# led_matrix_cc.net
KiCad netlist of a schematic drawn in EAGLE
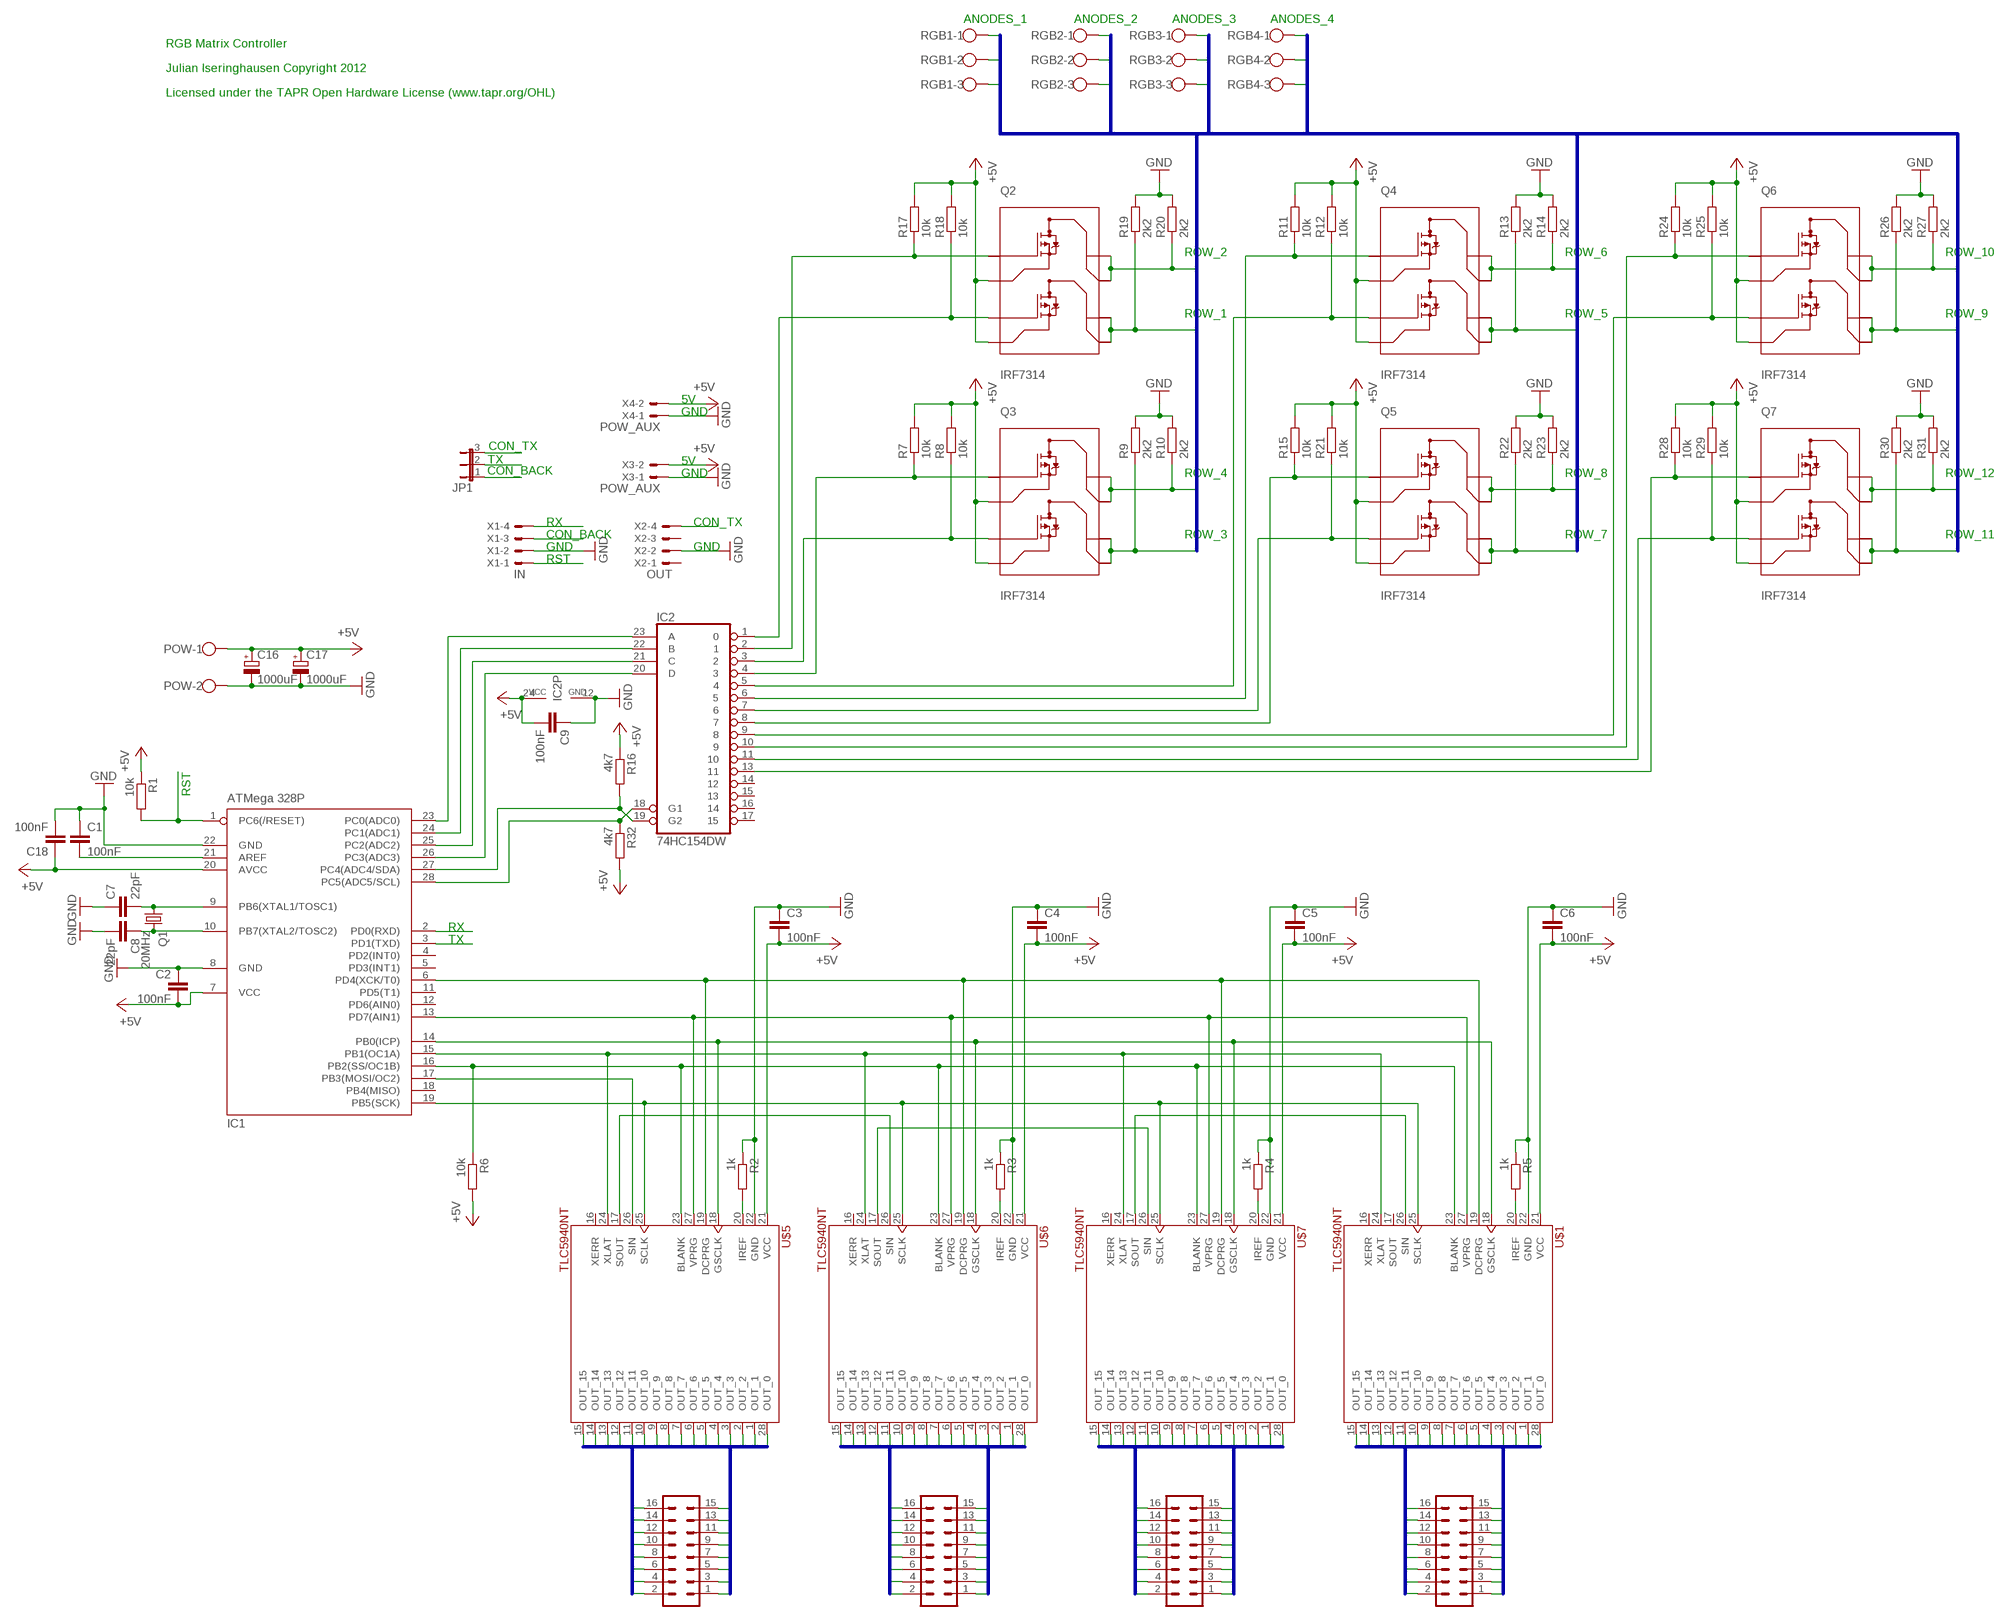
[diagram p0: schematic, sheet 1]

(export (version "E")
  (design (tool "Eeschema 10.0.6"))
  (components
    (comp (ref "C1")
      (value "100nF")
      (footprint "eagle-import:C1206")
      (libsource (lib "eagle-import") (part "C-EUC1206"))
    )
    (comp (ref "C2")
      (value "100nF")
      (footprint "eagle-import:C1206")
      (libsource (lib "eagle-import") (part "C-EUC1206"))
    )
    (comp (ref "C3")
      (value "100nF")
      (footprint "eagle-import:C1206")
      (libsource (lib "eagle-import") (part "C-EUC1206"))
    )
    (comp (ref "C4")
      (value "100nF")
      (footprint "eagle-import:C1206")
      (libsource (lib "eagle-import") (part "C-EUC1206"))
    )
    (comp (ref "C5")
      (value "100nF")
      (footprint "eagle-import:C1206")
      (libsource (lib "eagle-import") (part "C-EUC1206"))
    )
    (comp (ref "C6")
      (value "100nF")
      (footprint "eagle-import:C1206")
      (libsource (lib "eagle-import") (part "C-EUC1206"))
    )
    (comp (ref "C7")
      (value "22pF")
      (footprint "eagle-import:C1206")
      (libsource (lib "eagle-import") (part "C-EUC1206"))
    )
    (comp (ref "C8")
      (value "22pF")
      (footprint "eagle-import:C1206")
      (libsource (lib "eagle-import") (part "C-EUC1206"))
    )
    (comp (ref "C9")
      (value "100nF")
      (footprint "eagle-import:C1206")
      (libsource (lib "eagle-import") (part "C-EUC1206"))
    )
    (comp (ref "C16")
      (value "1000uF")
      (footprint "eagle-import:E5-10,5")
      (libsource (lib "eagle-import") (part "CPOL-EUE5-10.5"))
    )
    (comp (ref "C17")
      (value "1000uF")
      (footprint "eagle-import:E5-10,5")
      (libsource (lib "eagle-import") (part "CPOL-EUE5-10.5"))
    )
    (comp (ref "C18")
      (value "100nF")
      (footprint "eagle-import:C1206")
      (libsource (lib "eagle-import") (part "C-EUC1206"))
    )
    (comp (ref "CON_TLC_1")
      (value "ML16")
      (footprint "eagle-import:ML16")
      (libsource (lib "eagle-import") (part "ML16"))
    )
    (comp (ref "CON_TLC_2")
      (value "ML16")
      (footprint "eagle-import:ML16")
      (libsource (lib "eagle-import") (part "ML16"))
    )
    (comp (ref "CON_TLC_3")
      (value "ML16")
      (footprint "eagle-import:ML16")
      (libsource (lib "eagle-import") (part "ML16"))
    )
    (comp (ref "CON_TLC_4")
      (value "ML16")
      (footprint "eagle-import:ML16")
      (libsource (lib "eagle-import") (part "ML16"))
    )
    (comp (ref "IC1")
      (value "ATMega 328P")
      (footprint "eagle-import:DIL28-3")
      (libsource (lib "eagle-import") (part "MEGA8-P"))
    )
    (comp (ref "IC2")
      (value "74HC154DW")
      (footprint "eagle-import:SO24W")
      (libsource (lib "eagle-import") (part "74154DWHC"))
    )
    (comp (ref "JP1")
      (value "JP2E")
      (footprint "eagle-import:JP2")
      (libsource (lib "eagle-import") (part "JP2E"))
    )
    (comp (ref "POW")
      (value "W237-102")
      (footprint "eagle-import:W237-102")
      (fields (field (name "MPN") "237-102"))
      (libsource (lib "eagle-import") (part "W237-102"))
    )
    (comp (ref "Q1")
      (value "20MHz")
      (footprint "eagle-import:HC49U70")
      (libsource (lib "eagle-import") (part "CRYSTALHC49U70"))
    )
    (comp (ref "Q2")
      (value "IRF7314")
      (footprint "eagle-import:TRANSISTOR-FET-MOD_SO08-IRF")
      (libsource (lib "eagle-import") (part "TRANSISTOR-FET-MOD_IRF7389"))
    )
    (comp (ref "Q3")
      (value "IRF7314")
      (footprint "eagle-import:TRANSISTOR-FET-MOD_SO08-IRF")
      (libsource (lib "eagle-import") (part "TRANSISTOR-FET-MOD_IRF7389"))
    )
    (comp (ref "Q4")
      (value "IRF7314")
      (footprint "eagle-import:TRANSISTOR-FET-MOD_SO08-IRF")
      (libsource (lib "eagle-import") (part "TRANSISTOR-FET-MOD_IRF7389"))
    )
    (comp (ref "Q5")
      (value "IRF7314")
      (footprint "eagle-import:TRANSISTOR-FET-MOD_SO08-IRF")
      (libsource (lib "eagle-import") (part "TRANSISTOR-FET-MOD_IRF7389"))
    )
    (comp (ref "Q6")
      (value "IRF7314")
      (footprint "eagle-import:TRANSISTOR-FET-MOD_SO08-IRF")
      (libsource (lib "eagle-import") (part "TRANSISTOR-FET-MOD_IRF7389"))
    )
    (comp (ref "Q7")
      (value "IRF7314")
      (footprint "eagle-import:TRANSISTOR-FET-MOD_SO08-IRF")
      (libsource (lib "eagle-import") (part "TRANSISTOR-FET-MOD_IRF7389"))
    )
    (comp (ref "R1")
      (value "10k")
      (footprint "eagle-import:R1206")
      (libsource (lib "eagle-import") (part "R-EU_R1206"))
    )
    (comp (ref "R2")
      (value "1k")
      (footprint "eagle-import:R1206")
      (libsource (lib "eagle-import") (part "R-EU_R1206"))
    )
    (comp (ref "R3")
      (value "1k")
      (footprint "eagle-import:R1206")
      (libsource (lib "eagle-import") (part "R-EU_R1206"))
    )
    (comp (ref "R4")
      (value "1k")
      (footprint "eagle-import:R1206")
      (libsource (lib "eagle-import") (part "R-EU_R1206"))
    )
    (comp (ref "R5")
      (value "1k")
      (footprint "eagle-import:R1206")
      (libsource (lib "eagle-import") (part "R-EU_R1206"))
    )
    (comp (ref "R6")
      (value "10k")
      (footprint "eagle-import:R1206")
      (libsource (lib "eagle-import") (part "R-EU_R1206"))
    )
    (comp (ref "R7")
      (value "10k")
      (footprint "eagle-import:RCL_R1206")
      (libsource (lib "eagle-import") (part "RCL_R-EU_R1206"))
    )
    (comp (ref "R8")
      (value "10k")
      (footprint "eagle-import:RCL_R1206")
      (libsource (lib "eagle-import") (part "RCL_R-EU_R1206"))
    )
    (comp (ref "R9")
      (value "2k2")
      (footprint "eagle-import:RCL_R1206")
      (libsource (lib "eagle-import") (part "RCL_R-EU_R1206"))
    )
    (comp (ref "R10")
      (value "2k2")
      (footprint "eagle-import:RCL_R1206")
      (libsource (lib "eagle-import") (part "RCL_R-EU_R1206"))
    )
    (comp (ref "R11")
      (value "10k")
      (footprint "eagle-import:RCL_R1206")
      (libsource (lib "eagle-import") (part "RCL_R-EU_R1206"))
    )
    (comp (ref "R12")
      (value "10k")
      (footprint "eagle-import:RCL_R1206")
      (libsource (lib "eagle-import") (part "RCL_R-EU_R1206"))
    )
    (comp (ref "R13")
      (value "2k2")
      (footprint "eagle-import:RCL_R1206")
      (libsource (lib "eagle-import") (part "RCL_R-EU_R1206"))
    )
    (comp (ref "R14")
      (value "2k2")
      (footprint "eagle-import:RCL_R1206")
      (libsource (lib "eagle-import") (part "RCL_R-EU_R1206"))
    )
    (comp (ref "R15")
      (value "10k")
      (footprint "eagle-import:RCL_R1206")
      (libsource (lib "eagle-import") (part "RCL_R-EU_R1206"))
    )
    (comp (ref "R16")
      (value "4k7")
      (footprint "eagle-import:R1206")
      (libsource (lib "eagle-import") (part "R-EU_R1206"))
    )
    (comp (ref "R17")
      (value "10k")
      (footprint "eagle-import:RCL_R1206")
      (libsource (lib "eagle-import") (part "RCL_R-EU_R1206"))
    )
    (comp (ref "R18")
      (value "10k")
      (footprint "eagle-import:RCL_R1206")
      (libsource (lib "eagle-import") (part "RCL_R-EU_R1206"))
    )
    (comp (ref "R19")
      (value "2k2")
      (footprint "eagle-import:RCL_R1206")
      (libsource (lib "eagle-import") (part "RCL_R-EU_R1206"))
    )
    (comp (ref "R20")
      (value "2k2")
      (footprint "eagle-import:RCL_R1206")
      (libsource (lib "eagle-import") (part "RCL_R-EU_R1206"))
    )
    (comp (ref "R21")
      (value "10k")
      (footprint "eagle-import:RCL_R1206")
      (libsource (lib "eagle-import") (part "RCL_R-EU_R1206"))
    )
    (comp (ref "R22")
      (value "2k2")
      (footprint "eagle-import:RCL_R1206")
      (libsource (lib "eagle-import") (part "RCL_R-EU_R1206"))
    )
    (comp (ref "R23")
      (value "2k2")
      (footprint "eagle-import:RCL_R1206")
      (libsource (lib "eagle-import") (part "RCL_R-EU_R1206"))
    )
    (comp (ref "R24")
      (value "10k")
      (footprint "eagle-import:RCL_R1206")
      (libsource (lib "eagle-import") (part "RCL_R-EU_R1206"))
    )
    (comp (ref "R25")
      (value "10k")
      (footprint "eagle-import:RCL_R1206")
      (libsource (lib "eagle-import") (part "RCL_R-EU_R1206"))
    )
    (comp (ref "R26")
      (value "2k2")
      (footprint "eagle-import:RCL_R1206")
      (libsource (lib "eagle-import") (part "RCL_R-EU_R1206"))
    )
    (comp (ref "R27")
      (value "2k2")
      (footprint "eagle-import:RCL_R1206")
      (libsource (lib "eagle-import") (part "RCL_R-EU_R1206"))
    )
    (comp (ref "R28")
      (value "10k")
      (footprint "eagle-import:RCL_R1206")
      (libsource (lib "eagle-import") (part "RCL_R-EU_R1206"))
    )
    (comp (ref "R29")
      (value "10k")
      (footprint "eagle-import:RCL_R1206")
      (libsource (lib "eagle-import") (part "RCL_R-EU_R1206"))
    )
    (comp (ref "R30")
      (value "2k2")
      (footprint "eagle-import:RCL_R1206")
      (libsource (lib "eagle-import") (part "RCL_R-EU_R1206"))
    )
    (comp (ref "R31")
      (value "2k2")
      (footprint "eagle-import:RCL_R1206")
      (libsource (lib "eagle-import") (part "RCL_R-EU_R1206"))
    )
    (comp (ref "R32")
      (value "4k7")
      (footprint "eagle-import:R1206")
      (libsource (lib "eagle-import") (part "R-EU_R1206"))
    )
    (comp (ref "RGB1")
      (value "W237-103")
      (footprint "eagle-import:W237-103")
      (fields (field (name "MPN") "237-103"))
      (libsource (lib "eagle-import") (part "W237-103"))
    )
    (comp (ref "RGB2")
      (value "W237-103")
      (footprint "eagle-import:W237-103")
      (fields (field (name "MPN") "237-103"))
      (libsource (lib "eagle-import") (part "W237-103"))
    )
    (comp (ref "RGB3")
      (value "W237-103")
      (footprint "eagle-import:W237-103")
      (fields (field (name "MPN") "237-103"))
      (libsource (lib "eagle-import") (part "W237-103"))
    )
    (comp (ref "RGB4")
      (value "W237-103")
      (footprint "eagle-import:W237-103")
      (fields (field (name "MPN") "237-103"))
      (libsource (lib "eagle-import") (part "W237-103"))
    )
    (comp (ref "U$1")
      (value "TLC5940NT")
      (footprint "eagle-import:TLC5940_DIP-28")
      (libsource (lib "eagle-import") (part "TLC5940_TLC5940NT"))
    )
    (comp (ref "U$5")
      (value "TLC5940NT")
      (footprint "eagle-import:TLC5940_DIP-28")
      (libsource (lib "eagle-import") (part "TLC5940_TLC5940NT"))
    )
    (comp (ref "U$6")
      (value "TLC5940NT")
      (footprint "eagle-import:TLC5940_DIP-28")
      (libsource (lib "eagle-import") (part "TLC5940_TLC5940NT"))
    )
    (comp (ref "U$7")
      (value "TLC5940NT")
      (footprint "eagle-import:TLC5940_DIP-28")
      (libsource (lib "eagle-import") (part "TLC5940_TLC5940NT"))
    )
    (comp (ref "X1")
      (value "IN")
      (footprint "eagle-import:22-23-2041")
      (fields (field (name "MF") "MOLEX") (field (name "MPN") "22-23-2041"))
      (libsource (lib "eagle-import") (part "22-23-2041"))
    )
    (comp (ref "X2")
      (value "OUT")
      (footprint "eagle-import:22-23-2041")
      (fields (field (name "MF") "MOLEX") (field (name "MPN") "22-23-2041"))
      (libsource (lib "eagle-import") (part "22-23-2041"))
    )
    (comp (ref "X3")
      (value "POW_AUX")
      (footprint "eagle-import:22-23-2021")
      (fields (field (name "MF") "MOLEX") (field (name "MPN") "22-23-2021"))
      (libsource (lib "eagle-import") (part "22-23-2021"))
    )
    (comp (ref "X4")
      (value "POW_AUX")
      (footprint "eagle-import:22-23-2021")
      (fields (field (name "MF") "MOLEX") (field (name "MPN") "22-23-2021"))
      (libsource (lib "eagle-import") (part "22-23-2021"))
    )
  )
  (nets
    (net (code "1") (name "+5V") (class "Default")
      (node (ref "C16") (pin "+") (pinfunction "+_+") (pintype "passive"))
      (node (ref "C17") (pin "+") (pinfunction "+_+") (pintype "passive"))
      (node (ref "C18") (pin "1") (pinfunction "1_1") (pintype "passive"))
      (node (ref "C2") (pin "2") (pinfunction "2_2") (pintype "passive"))
      (node (ref "C3") (pin "2") (pinfunction "2_2") (pintype "passive"))
      (node (ref "C4") (pin "2") (pinfunction "2_2") (pintype "passive"))
      (node (ref "C5") (pin "2") (pinfunction "2_2") (pintype "passive"))
      (node (ref "C6") (pin "2") (pinfunction "2_2") (pintype "passive"))
      (node (ref "C9") (pin "2") (pinfunction "2_2") (pintype "passive"))
      (node (ref "IC1") (pin "20") (pinfunction "AVCC_20") (pintype "power_in"))
      (node (ref "IC1") (pin "7") (pinfunction "VCC_7") (pintype "power_in"))
      (node (ref "IC2") (pin "24") (pinfunction "VCC_24") (pintype "power_in"))
      (node (ref "POW") (pin "1") (pinfunction "KL_1") (pintype "passive"))
      (node (ref "Q2") (pin "1") (pinfunction "S1_1") (pintype "passive"))
      (node (ref "Q2") (pin "3") (pinfunction "S2_3") (pintype "passive"))
      (node (ref "Q3") (pin "1") (pinfunction "S1_1") (pintype "passive"))
      (node (ref "Q3") (pin "3") (pinfunction "S2_3") (pintype "passive"))
      (node (ref "Q4") (pin "1") (pinfunction "S1_1") (pintype "passive"))
      (node (ref "Q4") (pin "3") (pinfunction "S2_3") (pintype "passive"))
      (node (ref "Q5") (pin "1") (pinfunction "S1_1") (pintype "passive"))
      (node (ref "Q5") (pin "3") (pinfunction "S2_3") (pintype "passive"))
      (node (ref "Q6") (pin "1") (pinfunction "S1_1") (pintype "passive"))
      (node (ref "Q6") (pin "3") (pinfunction "S2_3") (pintype "passive"))
      (node (ref "Q7") (pin "1") (pinfunction "S1_1") (pintype "passive"))
      (node (ref "Q7") (pin "3") (pinfunction "S2_3") (pintype "passive"))
      (node (ref "R1") (pin "1") (pinfunction "1_1") (pintype "passive"))
      (node (ref "R11") (pin "2") (pinfunction "2_2") (pintype "passive"))
      (node (ref "R12") (pin "2") (pinfunction "2_2") (pintype "passive"))
      (node (ref "R15") (pin "2") (pinfunction "2_2") (pintype "passive"))
      (node (ref "R16") (pin "1") (pinfunction "1_1") (pintype "passive"))
      (node (ref "R17") (pin "2") (pinfunction "2_2") (pintype "passive"))
      (node (ref "R18") (pin "2") (pinfunction "2_2") (pintype "passive"))
      (node (ref "R21") (pin "2") (pinfunction "2_2") (pintype "passive"))
      (node (ref "R24") (pin "2") (pinfunction "2_2") (pintype "passive"))
      (node (ref "R25") (pin "2") (pinfunction "2_2") (pintype "passive"))
      (node (ref "R28") (pin "2") (pinfunction "2_2") (pintype "passive"))
      (node (ref "R29") (pin "2") (pinfunction "2_2") (pintype "passive"))
      (node (ref "R32") (pin "2") (pinfunction "2_2") (pintype "passive"))
      (node (ref "R6") (pin "2") (pinfunction "2_2") (pintype "passive"))
      (node (ref "R7") (pin "2") (pinfunction "2_2") (pintype "passive"))
      (node (ref "R8") (pin "2") (pinfunction "2_2") (pintype "passive"))
      (node (ref "U$1") (pin "21") (pinfunction "VCC_21") (pintype "power_in"))
      (node (ref "U$5") (pin "21") (pinfunction "VCC_21") (pintype "power_in"))
      (node (ref "U$6") (pin "21") (pinfunction "VCC_21") (pintype "power_in"))
      (node (ref "U$7") (pin "21") (pinfunction "VCC_21") (pintype "power_in"))
      (node (ref "X3") (pin "2") (pinfunction "S_2") (pintype "passive"))
      (node (ref "X4") (pin "2") (pinfunction "S_2") (pintype "passive"))
    )
    (net (code "2") (name "/CON_BACK") (class "Default")
      (node (ref "JP1") (pin "1") (pinfunction "1_1") (pintype "passive"))
      (node (ref "X1") (pin "3") (pinfunction "S_3") (pintype "passive"))
    )
    (net (code "3") (name "/CON_TX") (class "Default")
      (node (ref "JP1") (pin "3") (pinfunction "3_3") (pintype "passive"))
      (node (ref "X2") (pin "4") (pinfunction "S_4") (pintype "passive"))
    )
    (net (code "4") (name "/ROW1") (class "Default")
      (node (ref "Q2") (pin "5") (pinfunction "D2B_5") (pintype "passive"))
      (node (ref "Q2") (pin "6") (pinfunction "D2A_6") (pintype "passive"))
      (node (ref "R19") (pin "1") (pinfunction "1_1") (pintype "passive"))
      (node (ref "RGB1") (pin "1") (pinfunction "KL_1") (pintype "passive"))
    )
    (net (code "5") (name "/ROW2") (class "Default")
      (node (ref "Q2") (pin "7") (pinfunction "D1B_7") (pintype "passive"))
      (node (ref "Q2") (pin "8") (pinfunction "D1A_8") (pintype "passive"))
      (node (ref "R20") (pin "1") (pinfunction "1_1") (pintype "passive"))
      (node (ref "RGB1") (pin "2") (pinfunction "KL_2") (pintype "passive"))
    )
    (net (code "6") (name "/ROW3") (class "Default")
      (node (ref "Q3") (pin "5") (pinfunction "D2B_5") (pintype "passive"))
      (node (ref "Q3") (pin "6") (pinfunction "D2A_6") (pintype "passive"))
      (node (ref "R9") (pin "1") (pinfunction "1_1") (pintype "passive"))
      (node (ref "RGB1") (pin "3") (pinfunction "KL_3") (pintype "passive"))
    )
    (net (code "7") (name "/ROW4") (class "Default")
      (node (ref "Q3") (pin "7") (pinfunction "D1B_7") (pintype "passive"))
      (node (ref "Q3") (pin "8") (pinfunction "D1A_8") (pintype "passive"))
      (node (ref "R10") (pin "1") (pinfunction "1_1") (pintype "passive"))
      (node (ref "RGB2") (pin "1") (pinfunction "KL_1") (pintype "passive"))
    )
    (net (code "8") (name "/ROW5") (class "Default")
      (node (ref "Q4") (pin "5") (pinfunction "D2B_5") (pintype "passive"))
      (node (ref "Q4") (pin "6") (pinfunction "D2A_6") (pintype "passive"))
      (node (ref "R13") (pin "1") (pinfunction "1_1") (pintype "passive"))
      (node (ref "RGB2") (pin "2") (pinfunction "KL_2") (pintype "passive"))
    )
    (net (code "9") (name "/ROW6") (class "Default")
      (node (ref "Q4") (pin "7") (pinfunction "D1B_7") (pintype "passive"))
      (node (ref "Q4") (pin "8") (pinfunction "D1A_8") (pintype "passive"))
      (node (ref "R14") (pin "1") (pinfunction "1_1") (pintype "passive"))
      (node (ref "RGB2") (pin "3") (pinfunction "KL_3") (pintype "passive"))
    )
    (net (code "10") (name "/ROW7") (class "Default")
      (node (ref "Q5") (pin "5") (pinfunction "D2B_5") (pintype "passive"))
      (node (ref "Q5") (pin "6") (pinfunction "D2A_6") (pintype "passive"))
      (node (ref "R22") (pin "1") (pinfunction "1_1") (pintype "passive"))
      (node (ref "RGB3") (pin "1") (pinfunction "KL_1") (pintype "passive"))
    )
    (net (code "11") (name "/ROW8") (class "Default")
      (node (ref "Q5") (pin "7") (pinfunction "D1B_7") (pintype "passive"))
      (node (ref "Q5") (pin "8") (pinfunction "D1A_8") (pintype "passive"))
      (node (ref "R23") (pin "1") (pinfunction "1_1") (pintype "passive"))
      (node (ref "RGB3") (pin "2") (pinfunction "KL_2") (pintype "passive"))
    )
    (net (code "12") (name "/ROW9") (class "Default")
      (node (ref "Q6") (pin "5") (pinfunction "D2B_5") (pintype "passive"))
      (node (ref "Q6") (pin "6") (pinfunction "D2A_6") (pintype "passive"))
      (node (ref "R26") (pin "1") (pinfunction "1_1") (pintype "passive"))
      (node (ref "RGB3") (pin "3") (pinfunction "KL_3") (pintype "passive"))
    )
    (net (code "13") (name "/ROW10") (class "Default")
      (node (ref "Q6") (pin "7") (pinfunction "D1B_7") (pintype "passive"))
      (node (ref "Q6") (pin "8") (pinfunction "D1A_8") (pintype "passive"))
      (node (ref "R27") (pin "1") (pinfunction "1_1") (pintype "passive"))
      (node (ref "RGB4") (pin "1") (pinfunction "KL_1") (pintype "passive"))
    )
    (net (code "14") (name "/ROW11") (class "Default")
      (node (ref "Q7") (pin "5") (pinfunction "D2B_5") (pintype "passive"))
      (node (ref "Q7") (pin "6") (pinfunction "D2A_6") (pintype "passive"))
      (node (ref "R30") (pin "1") (pinfunction "1_1") (pintype "passive"))
      (node (ref "RGB4") (pin "2") (pinfunction "KL_2") (pintype "passive"))
    )
    (net (code "15") (name "/ROW12") (class "Default")
      (node (ref "Q7") (pin "7") (pinfunction "D1B_7") (pintype "passive"))
      (node (ref "Q7") (pin "8") (pinfunction "D1A_8") (pintype "passive"))
      (node (ref "R31") (pin "1") (pinfunction "1_1") (pintype "passive"))
      (node (ref "RGB4") (pin "3") (pinfunction "KL_3") (pintype "passive"))
    )
    (net (code "16") (name "/RST") (class "Default")
      (node (ref "IC1") (pin "1") (pinfunction "PC6(/RESET)_1") (pintype "bidirectional"))
      (node (ref "R1") (pin "2") (pinfunction "2_2") (pintype "passive"))
      (node (ref "X1") (pin "1") (pinfunction "S_1") (pintype "passive"))
    )
    (net (code "17") (name "/RX") (class "Default")
      (node (ref "IC1") (pin "2") (pinfunction "PD0(RXD)_2") (pintype "bidirectional"))
      (node (ref "X1") (pin "4") (pinfunction "S_4") (pintype "passive"))
    )
    (net (code "18") (name "/T1_1") (class "Default")
      (node (ref "CON_TLC_1") (pin "1") (pinfunction "1_1") (pintype "passive"))
      (node (ref "U$5") (pin "28") (pinfunction "OUT_0_28") (pintype "output"))
    )
    (net (code "19") (name "/T1_2") (class "Default")
      (node (ref "CON_TLC_1") (pin "2") (pinfunction "2_2") (pintype "passive"))
      (node (ref "U$5") (pin "1") (pinfunction "OUT_1_1") (pintype "output"))
    )
    (net (code "20") (name "/T1_3") (class "Default")
      (node (ref "CON_TLC_1") (pin "3") (pinfunction "3_3") (pintype "passive"))
      (node (ref "U$5") (pin "2") (pinfunction "OUT_2_2") (pintype "output"))
    )
    (net (code "21") (name "/T1_4") (class "Default")
      (node (ref "CON_TLC_1") (pin "4") (pinfunction "4_4") (pintype "passive"))
      (node (ref "U$5") (pin "3") (pinfunction "OUT_3_3") (pintype "output"))
    )
    (net (code "22") (name "/T1_5") (class "Default")
      (node (ref "CON_TLC_1") (pin "5") (pinfunction "5_5") (pintype "passive"))
      (node (ref "U$5") (pin "4") (pinfunction "OUT_4_4") (pintype "output"))
    )
    (net (code "23") (name "/T1_6") (class "Default")
      (node (ref "CON_TLC_1") (pin "6") (pinfunction "6_6") (pintype "passive"))
      (node (ref "U$5") (pin "5") (pinfunction "OUT_5_5") (pintype "output"))
    )
    (net (code "24") (name "/T1_7") (class "Default")
      (node (ref "CON_TLC_1") (pin "7") (pinfunction "7_7") (pintype "passive"))
      (node (ref "U$5") (pin "6") (pinfunction "OUT_6_6") (pintype "output"))
    )
    (net (code "25") (name "/T1_8") (class "Default")
      (node (ref "CON_TLC_1") (pin "8") (pinfunction "8_8") (pintype "passive"))
      (node (ref "U$5") (pin "7") (pinfunction "OUT_7_7") (pintype "output"))
    )
    (net (code "26") (name "/T1_9") (class "Default")
      (node (ref "CON_TLC_1") (pin "9") (pinfunction "9_9") (pintype "passive"))
      (node (ref "U$5") (pin "8") (pinfunction "OUT_8_8") (pintype "output"))
    )
    (net (code "27") (name "/T1_10") (class "Default")
      (node (ref "CON_TLC_1") (pin "10") (pinfunction "10_10") (pintype "passive"))
      (node (ref "U$5") (pin "9") (pinfunction "OUT_9_9") (pintype "output"))
    )
    (net (code "28") (name "/T1_11") (class "Default")
      (node (ref "CON_TLC_1") (pin "11") (pinfunction "11_11") (pintype "passive"))
      (node (ref "U$5") (pin "10") (pinfunction "OUT_10_10") (pintype "output"))
    )
    (net (code "29") (name "/T1_12") (class "Default")
      (node (ref "CON_TLC_1") (pin "12") (pinfunction "12_12") (pintype "passive"))
      (node (ref "U$5") (pin "11") (pinfunction "OUT_11_11") (pintype "output"))
    )
    (net (code "30") (name "/T1_13") (class "Default")
      (node (ref "CON_TLC_1") (pin "13") (pinfunction "13_13") (pintype "passive"))
      (node (ref "U$5") (pin "12") (pinfunction "OUT_12_12") (pintype "output"))
    )
    (net (code "31") (name "/T1_14") (class "Default")
      (node (ref "CON_TLC_1") (pin "14") (pinfunction "14_14") (pintype "passive"))
      (node (ref "U$5") (pin "13") (pinfunction "OUT_13_13") (pintype "output"))
    )
    (net (code "32") (name "/T1_15") (class "Default")
      (node (ref "CON_TLC_1") (pin "15") (pinfunction "15_15") (pintype "passive"))
      (node (ref "U$5") (pin "14") (pinfunction "OUT_14_14") (pintype "output"))
    )
    (net (code "33") (name "/T1_16") (class "Default")
      (node (ref "CON_TLC_1") (pin "16") (pinfunction "16_16") (pintype "passive"))
      (node (ref "U$5") (pin "15") (pinfunction "OUT_15_15") (pintype "output"))
    )
    (net (code "34") (name "/T2_1") (class "Default")
      (node (ref "CON_TLC_2") (pin "1") (pinfunction "1_1") (pintype "passive"))
      (node (ref "U$6") (pin "28") (pinfunction "OUT_0_28") (pintype "output"))
    )
    (net (code "35") (name "/T2_2") (class "Default")
      (node (ref "CON_TLC_2") (pin "2") (pinfunction "2_2") (pintype "passive"))
      (node (ref "U$6") (pin "1") (pinfunction "OUT_1_1") (pintype "output"))
    )
    (net (code "36") (name "/T2_3") (class "Default")
      (node (ref "CON_TLC_2") (pin "3") (pinfunction "3_3") (pintype "passive"))
      (node (ref "U$6") (pin "2") (pinfunction "OUT_2_2") (pintype "output"))
    )
    (net (code "37") (name "/T2_4") (class "Default")
      (node (ref "CON_TLC_2") (pin "4") (pinfunction "4_4") (pintype "passive"))
      (node (ref "U$6") (pin "3") (pinfunction "OUT_3_3") (pintype "output"))
    )
    (net (code "38") (name "/T2_5") (class "Default")
      (node (ref "CON_TLC_2") (pin "5") (pinfunction "5_5") (pintype "passive"))
      (node (ref "U$6") (pin "4") (pinfunction "OUT_4_4") (pintype "output"))
    )
    (net (code "39") (name "/T2_6") (class "Default")
      (node (ref "CON_TLC_2") (pin "6") (pinfunction "6_6") (pintype "passive"))
      (node (ref "U$6") (pin "5") (pinfunction "OUT_5_5") (pintype "output"))
    )
    (net (code "40") (name "/T2_7") (class "Default")
      (node (ref "CON_TLC_2") (pin "7") (pinfunction "7_7") (pintype "passive"))
      (node (ref "U$6") (pin "6") (pinfunction "OUT_6_6") (pintype "output"))
    )
    (net (code "41") (name "/T2_8") (class "Default")
      (node (ref "CON_TLC_2") (pin "8") (pinfunction "8_8") (pintype "passive"))
      (node (ref "U$6") (pin "7") (pinfunction "OUT_7_7") (pintype "output"))
    )
    (net (code "42") (name "/T2_9") (class "Default")
      (node (ref "CON_TLC_2") (pin "9") (pinfunction "9_9") (pintype "passive"))
      (node (ref "U$6") (pin "8") (pinfunction "OUT_8_8") (pintype "output"))
    )
    (net (code "43") (name "/T2_10") (class "Default")
      (node (ref "CON_TLC_2") (pin "10") (pinfunction "10_10") (pintype "passive"))
      (node (ref "U$6") (pin "9") (pinfunction "OUT_9_9") (pintype "output"))
    )
    (net (code "44") (name "/T2_11") (class "Default")
      (node (ref "CON_TLC_2") (pin "11") (pinfunction "11_11") (pintype "passive"))
      (node (ref "U$6") (pin "10") (pinfunction "OUT_10_10") (pintype "output"))
    )
    (net (code "45") (name "/T2_12") (class "Default")
      (node (ref "CON_TLC_2") (pin "12") (pinfunction "12_12") (pintype "passive"))
      (node (ref "U$6") (pin "11") (pinfunction "OUT_11_11") (pintype "output"))
    )
    (net (code "46") (name "/T2_13") (class "Default")
      (node (ref "CON_TLC_2") (pin "13") (pinfunction "13_13") (pintype "passive"))
      (node (ref "U$6") (pin "12") (pinfunction "OUT_12_12") (pintype "output"))
    )
    (net (code "47") (name "/T2_14") (class "Default")
      (node (ref "CON_TLC_2") (pin "14") (pinfunction "14_14") (pintype "passive"))
      (node (ref "U$6") (pin "13") (pinfunction "OUT_13_13") (pintype "output"))
    )
    (net (code "48") (name "/T2_15") (class "Default")
      (node (ref "CON_TLC_2") (pin "15") (pinfunction "15_15") (pintype "passive"))
      (node (ref "U$6") (pin "14") (pinfunction "OUT_14_14") (pintype "output"))
    )
    (net (code "49") (name "/T2_16") (class "Default")
      (node (ref "CON_TLC_2") (pin "16") (pinfunction "16_16") (pintype "passive"))
      (node (ref "U$6") (pin "15") (pinfunction "OUT_15_15") (pintype "output"))
    )
    (net (code "50") (name "/T3_1") (class "Default")
      (node (ref "CON_TLC_3") (pin "1") (pinfunction "1_1") (pintype "passive"))
      (node (ref "U$7") (pin "28") (pinfunction "OUT_0_28") (pintype "output"))
    )
    (net (code "51") (name "/T3_2") (class "Default")
      (node (ref "CON_TLC_3") (pin "2") (pinfunction "2_2") (pintype "passive"))
      (node (ref "U$7") (pin "1") (pinfunction "OUT_1_1") (pintype "output"))
    )
    (net (code "52") (name "/T3_3") (class "Default")
      (node (ref "CON_TLC_3") (pin "3") (pinfunction "3_3") (pintype "passive"))
      (node (ref "U$7") (pin "2") (pinfunction "OUT_2_2") (pintype "output"))
    )
    (net (code "53") (name "/T3_4") (class "Default")
      (node (ref "CON_TLC_3") (pin "4") (pinfunction "4_4") (pintype "passive"))
      (node (ref "U$7") (pin "3") (pinfunction "OUT_3_3") (pintype "output"))
    )
    (net (code "54") (name "/T3_5") (class "Default")
      (node (ref "CON_TLC_3") (pin "5") (pinfunction "5_5") (pintype "passive"))
      (node (ref "U$7") (pin "4") (pinfunction "OUT_4_4") (pintype "output"))
    )
    (net (code "55") (name "/T3_6") (class "Default")
      (node (ref "CON_TLC_3") (pin "6") (pinfunction "6_6") (pintype "passive"))
      (node (ref "U$7") (pin "5") (pinfunction "OUT_5_5") (pintype "output"))
    )
    (net (code "56") (name "/T3_7") (class "Default")
      (node (ref "CON_TLC_3") (pin "7") (pinfunction "7_7") (pintype "passive"))
      (node (ref "U$7") (pin "6") (pinfunction "OUT_6_6") (pintype "output"))
    )
    (net (code "57") (name "/T3_8") (class "Default")
      (node (ref "CON_TLC_3") (pin "8") (pinfunction "8_8") (pintype "passive"))
      (node (ref "U$7") (pin "7") (pinfunction "OUT_7_7") (pintype "output"))
    )
    (net (code "58") (name "/T3_9") (class "Default")
      (node (ref "CON_TLC_3") (pin "9") (pinfunction "9_9") (pintype "passive"))
      (node (ref "U$7") (pin "8") (pinfunction "OUT_8_8") (pintype "output"))
    )
    (net (code "59") (name "/T3_10") (class "Default")
      (node (ref "CON_TLC_3") (pin "10") (pinfunction "10_10") (pintype "passive"))
      (node (ref "U$7") (pin "9") (pinfunction "OUT_9_9") (pintype "output"))
    )
    (net (code "60") (name "/T3_11") (class "Default")
      (node (ref "CON_TLC_3") (pin "11") (pinfunction "11_11") (pintype "passive"))
      (node (ref "U$7") (pin "10") (pinfunction "OUT_10_10") (pintype "output"))
    )
    (net (code "61") (name "/T3_12") (class "Default")
      (node (ref "CON_TLC_3") (pin "12") (pinfunction "12_12") (pintype "passive"))
      (node (ref "U$7") (pin "11") (pinfunction "OUT_11_11") (pintype "output"))
    )
    (net (code "62") (name "/T3_13") (class "Default")
      (node (ref "CON_TLC_3") (pin "13") (pinfunction "13_13") (pintype "passive"))
      (node (ref "U$7") (pin "12") (pinfunction "OUT_12_12") (pintype "output"))
    )
    (net (code "63") (name "/T3_14") (class "Default")
      (node (ref "CON_TLC_3") (pin "14") (pinfunction "14_14") (pintype "passive"))
      (node (ref "U$7") (pin "13") (pinfunction "OUT_13_13") (pintype "output"))
    )
    (net (code "64") (name "/T3_15") (class "Default")
      (node (ref "CON_TLC_3") (pin "15") (pinfunction "15_15") (pintype "passive"))
      (node (ref "U$7") (pin "14") (pinfunction "OUT_14_14") (pintype "output"))
    )
    (net (code "65") (name "/T3_16") (class "Default")
      (node (ref "CON_TLC_3") (pin "16") (pinfunction "16_16") (pintype "passive"))
      (node (ref "U$7") (pin "15") (pinfunction "OUT_15_15") (pintype "output"))
    )
    (net (code "66") (name "/T4_1") (class "Default")
      (node (ref "CON_TLC_4") (pin "1") (pinfunction "1_1") (pintype "passive"))
      (node (ref "U$1") (pin "28") (pinfunction "OUT_0_28") (pintype "output"))
    )
    (net (code "67") (name "/T4_2") (class "Default")
      (node (ref "CON_TLC_4") (pin "2") (pinfunction "2_2") (pintype "passive"))
      (node (ref "U$1") (pin "1") (pinfunction "OUT_1_1") (pintype "output"))
    )
    (net (code "68") (name "/T4_3") (class "Default")
      (node (ref "CON_TLC_4") (pin "3") (pinfunction "3_3") (pintype "passive"))
      (node (ref "U$1") (pin "2") (pinfunction "OUT_2_2") (pintype "output"))
    )
    (net (code "69") (name "/T4_4") (class "Default")
      (node (ref "CON_TLC_4") (pin "4") (pinfunction "4_4") (pintype "passive"))
      (node (ref "U$1") (pin "3") (pinfunction "OUT_3_3") (pintype "output"))
    )
    (net (code "70") (name "/T4_5") (class "Default")
      (node (ref "CON_TLC_4") (pin "5") (pinfunction "5_5") (pintype "passive"))
      (node (ref "U$1") (pin "4") (pinfunction "OUT_4_4") (pintype "output"))
    )
    (net (code "71") (name "/T4_6") (class "Default")
      (node (ref "CON_TLC_4") (pin "6") (pinfunction "6_6") (pintype "passive"))
      (node (ref "U$1") (pin "5") (pinfunction "OUT_5_5") (pintype "output"))
    )
    (net (code "72") (name "/T4_7") (class "Default")
      (node (ref "CON_TLC_4") (pin "7") (pinfunction "7_7") (pintype "passive"))
      (node (ref "U$1") (pin "6") (pinfunction "OUT_6_6") (pintype "output"))
    )
    (net (code "73") (name "/T4_8") (class "Default")
      (node (ref "CON_TLC_4") (pin "8") (pinfunction "8_8") (pintype "passive"))
      (node (ref "U$1") (pin "7") (pinfunction "OUT_7_7") (pintype "output"))
    )
    (net (code "74") (name "/T4_9") (class "Default")
      (node (ref "CON_TLC_4") (pin "9") (pinfunction "9_9") (pintype "passive"))
      (node (ref "U$1") (pin "8") (pinfunction "OUT_8_8") (pintype "output"))
    )
    (net (code "75") (name "/T4_10") (class "Default")
      (node (ref "CON_TLC_4") (pin "10") (pinfunction "10_10") (pintype "passive"))
      (node (ref "U$1") (pin "9") (pinfunction "OUT_9_9") (pintype "output"))
    )
    (net (code "76") (name "/T4_11") (class "Default")
      (node (ref "CON_TLC_4") (pin "11") (pinfunction "11_11") (pintype "passive"))
      (node (ref "U$1") (pin "10") (pinfunction "OUT_10_10") (pintype "output"))
    )
    (net (code "77") (name "/T4_12") (class "Default")
      (node (ref "CON_TLC_4") (pin "12") (pinfunction "12_12") (pintype "passive"))
      (node (ref "U$1") (pin "11") (pinfunction "OUT_11_11") (pintype "output"))
    )
    (net (code "78") (name "/T4_13") (class "Default")
      (node (ref "CON_TLC_4") (pin "13") (pinfunction "13_13") (pintype "passive"))
      (node (ref "U$1") (pin "12") (pinfunction "OUT_12_12") (pintype "output"))
    )
    (net (code "79") (name "/T4_14") (class "Default")
      (node (ref "CON_TLC_4") (pin "14") (pinfunction "14_14") (pintype "passive"))
      (node (ref "U$1") (pin "13") (pinfunction "OUT_13_13") (pintype "output"))
    )
    (net (code "80") (name "/T4_15") (class "Default")
      (node (ref "CON_TLC_4") (pin "15") (pinfunction "15_15") (pintype "passive"))
      (node (ref "U$1") (pin "14") (pinfunction "OUT_14_14") (pintype "output"))
    )
    (net (code "81") (name "/T4_16") (class "Default")
      (node (ref "CON_TLC_4") (pin "16") (pinfunction "16_16") (pintype "passive"))
      (node (ref "U$1") (pin "15") (pinfunction "OUT_15_15") (pintype "output"))
    )
    (net (code "82") (name "/TX") (class "Default")
      (node (ref "IC1") (pin "3") (pinfunction "PD1(TXD)_3") (pintype "bidirectional"))
      (node (ref "JP1") (pin "2") (pinfunction "2_2") (pintype "passive"))
    )
    (net (code "83") (name "GND") (class "Default")
      (node (ref "C1") (pin "1") (pinfunction "1_1") (pintype "passive"))
      (node (ref "C16") (pin "-") (pinfunction "-_-") (pintype "passive"))
      (node (ref "C17") (pin "-") (pinfunction "-_-") (pintype "passive"))
      (node (ref "C18") (pin "2") (pinfunction "2_2") (pintype "passive"))
      (node (ref "C2") (pin "1") (pinfunction "1_1") (pintype "passive"))
      (node (ref "C3") (pin "1") (pinfunction "1_1") (pintype "passive"))
      (node (ref "C4") (pin "1") (pinfunction "1_1") (pintype "passive"))
      (node (ref "C5") (pin "1") (pinfunction "1_1") (pintype "passive"))
      (node (ref "C6") (pin "1") (pinfunction "1_1") (pintype "passive"))
      (node (ref "C7") (pin "1") (pinfunction "1_1") (pintype "passive"))
      (node (ref "C8") (pin "2") (pinfunction "2_2") (pintype "passive"))
      (node (ref "C9") (pin "1") (pinfunction "1_1") (pintype "passive"))
      (node (ref "IC1") (pin "22") (pinfunction "GND_22") (pintype "power_in"))
      (node (ref "IC1") (pin "8") (pinfunction "GND_8") (pintype "power_in"))
      (node (ref "IC2") (pin "12") (pinfunction "GND_12") (pintype "power_in"))
      (node (ref "POW") (pin "2") (pinfunction "KL_2") (pintype "passive"))
      (node (ref "R10") (pin "2") (pinfunction "2_2") (pintype "passive"))
      (node (ref "R13") (pin "2") (pinfunction "2_2") (pintype "passive"))
      (node (ref "R14") (pin "2") (pinfunction "2_2") (pintype "passive"))
      (node (ref "R19") (pin "2") (pinfunction "2_2") (pintype "passive"))
      (node (ref "R2") (pin "1") (pinfunction "1_1") (pintype "passive"))
      (node (ref "R20") (pin "2") (pinfunction "2_2") (pintype "passive"))
      (node (ref "R22") (pin "2") (pinfunction "2_2") (pintype "passive"))
      (node (ref "R23") (pin "2") (pinfunction "2_2") (pintype "passive"))
      (node (ref "R26") (pin "2") (pinfunction "2_2") (pintype "passive"))
      (node (ref "R27") (pin "2") (pinfunction "2_2") (pintype "passive"))
      (node (ref "R3") (pin "1") (pinfunction "1_1") (pintype "passive"))
      (node (ref "R30") (pin "2") (pinfunction "2_2") (pintype "passive"))
      (node (ref "R31") (pin "2") (pinfunction "2_2") (pintype "passive"))
      (node (ref "R4") (pin "1") (pinfunction "1_1") (pintype "passive"))
      (node (ref "R5") (pin "1") (pinfunction "1_1") (pintype "passive"))
      (node (ref "R9") (pin "2") (pinfunction "2_2") (pintype "passive"))
      (node (ref "U$1") (pin "22") (pinfunction "GND_22") (pintype "power_in"))
      (node (ref "U$5") (pin "22") (pinfunction "GND_22") (pintype "power_in"))
      (node (ref "U$6") (pin "22") (pinfunction "GND_22") (pintype "power_in"))
      (node (ref "U$7") (pin "22") (pinfunction "GND_22") (pintype "power_in"))
      (node (ref "X1") (pin "2") (pinfunction "S_2") (pintype "passive"))
      (node (ref "X2") (pin "2") (pinfunction "S_2") (pintype "passive"))
      (node (ref "X3") (pin "1") (pinfunction "S_1") (pintype "passive"))
      (node (ref "X4") (pin "1") (pinfunction "S_1") (pintype "passive"))
    )
    (net (code "84") (name "Net-(IC1-AREF)") (class "Default")
      (node (ref "C1") (pin "2") (pinfunction "2_2") (pintype "passive"))
      (node (ref "IC1") (pin "21") (pinfunction "AREF_21") (pintype "passive"))
    )
    (net (code "85") (name "Net-(IC1-PB0(ICP))") (class "Default")
      (node (ref "IC1") (pin "14") (pinfunction "PB0(ICP)_14") (pintype "bidirectional"))
      (node (ref "U$1") (pin "18") (pinfunction "GSCLK_18") (pintype "input"))
      (node (ref "U$5") (pin "18") (pinfunction "GSCLK_18") (pintype "input"))
      (node (ref "U$6") (pin "18") (pinfunction "GSCLK_18") (pintype "input"))
      (node (ref "U$7") (pin "18") (pinfunction "GSCLK_18") (pintype "input"))
    )
    (net (code "86") (name "Net-(IC1-PB1(OC1A))") (class "Default")
      (node (ref "IC1") (pin "15") (pinfunction "PB1(OC1A)_15") (pintype "bidirectional"))
      (node (ref "U$1") (pin "24") (pinfunction "XLAT_24") (pintype "input"))
      (node (ref "U$5") (pin "24") (pinfunction "XLAT_24") (pintype "input"))
      (node (ref "U$6") (pin "24") (pinfunction "XLAT_24") (pintype "input"))
      (node (ref "U$7") (pin "24") (pinfunction "XLAT_24") (pintype "input"))
    )
    (net (code "87") (name "Net-(IC1-PB2(SS{slash}OC1B))") (class "Default")
      (node (ref "IC1") (pin "16") (pinfunction "PB2(SS/OC1B)_16") (pintype "bidirectional"))
      (node (ref "R6") (pin "1") (pinfunction "1_1") (pintype "passive"))
      (node (ref "U$1") (pin "23") (pinfunction "BLANK_23") (pintype "input"))
      (node (ref "U$5") (pin "23") (pinfunction "BLANK_23") (pintype "input"))
      (node (ref "U$6") (pin "23") (pinfunction "BLANK_23") (pintype "input"))
      (node (ref "U$7") (pin "23") (pinfunction "BLANK_23") (pintype "input"))
    )
    (net (code "88") (name "Net-(IC1-PB3(MOSI{slash}OC2))") (class "Default")
      (node (ref "IC1") (pin "17") (pinfunction "PB3(MOSI/OC2)_17") (pintype "bidirectional"))
      (node (ref "U$5") (pin "26") (pinfunction "SIN_26") (pintype "input"))
    )
    (net (code "89") (name "Net-(IC1-PB5(SCK))") (class "Default")
      (node (ref "IC1") (pin "19") (pinfunction "PB5(SCK)_19") (pintype "bidirectional"))
      (node (ref "U$1") (pin "25") (pinfunction "SCLK_25") (pintype "input"))
      (node (ref "U$5") (pin "25") (pinfunction "SCLK_25") (pintype "input"))
      (node (ref "U$6") (pin "25") (pinfunction "SCLK_25") (pintype "input"))
      (node (ref "U$7") (pin "25") (pinfunction "SCLK_25") (pintype "input"))
    )
    (net (code "90") (name "Net-(IC1-PB6(XTAL1{slash}TOSC1))") (class "Default")
      (node (ref "C7") (pin "2") (pinfunction "2_2") (pintype "passive"))
      (node (ref "IC1") (pin "9") (pinfunction "PB6(XTAL1/TOSC1)_9") (pintype "bidirectional"))
      (node (ref "Q1") (pin "1") (pinfunction "1_1") (pintype "passive"))
    )
    (net (code "91") (name "Net-(IC1-PB7(XTAL2{slash}TOSC2))") (class "Default")
      (node (ref "C8") (pin "1") (pinfunction "1_1") (pintype "passive"))
      (node (ref "IC1") (pin "10") (pinfunction "PB7(XTAL2/TOSC2)_10") (pintype "bidirectional"))
      (node (ref "Q1") (pin "2") (pinfunction "2_2") (pintype "passive"))
    )
    (net (code "92") (name "Net-(IC1-PC0(ADC0))") (class "Default")
      (node (ref "IC1") (pin "23") (pinfunction "PC0(ADC0)_23") (pintype "bidirectional"))
      (node (ref "IC2") (pin "23") (pinfunction "A_23") (pintype "input"))
    )
    (net (code "93") (name "Net-(IC1-PC1(ADC1))") (class "Default")
      (node (ref "IC1") (pin "24") (pinfunction "PC1(ADC1)_24") (pintype "bidirectional"))
      (node (ref "IC2") (pin "22") (pinfunction "B_22") (pintype "input"))
    )
    (net (code "94") (name "Net-(IC1-PC2(ADC2))") (class "Default")
      (node (ref "IC1") (pin "25") (pinfunction "PC2(ADC2)_25") (pintype "bidirectional"))
      (node (ref "IC2") (pin "21") (pinfunction "C_21") (pintype "input"))
    )
    (net (code "95") (name "Net-(IC1-PC3(ADC3))") (class "Default")
      (node (ref "IC1") (pin "26") (pinfunction "PC3(ADC3)_26") (pintype "bidirectional"))
      (node (ref "IC2") (pin "20") (pinfunction "D_20") (pintype "input"))
    )
    (net (code "96") (name "Net-(IC1-PC4(ADC4{slash}SDA))") (class "Default")
      (node (ref "IC1") (pin "27") (pinfunction "PC4(ADC4/SDA)_27") (pintype "bidirectional"))
      (node (ref "IC2") (pin "19") (pinfunction "G2_19") (pintype "input"))
      (node (ref "R16") (pin "2") (pinfunction "2_2") (pintype "passive"))
    )
    (net (code "97") (name "Net-(IC1-PC5(ADC5{slash}SCL))") (class "Default")
      (node (ref "IC1") (pin "28") (pinfunction "PC5(ADC5/SCL)_28") (pintype "bidirectional"))
      (node (ref "IC2") (pin "18") (pinfunction "G1_18") (pintype "input"))
      (node (ref "R32") (pin "1") (pinfunction "1_1") (pintype "passive"))
    )
    (net (code "98") (name "Net-(IC1-PD4(XCK{slash}T0))") (class "Default")
      (node (ref "IC1") (pin "6") (pinfunction "PD4(XCK/T0)_6") (pintype "bidirectional"))
      (node (ref "U$1") (pin "19") (pinfunction "DCPRG_19") (pintype "input"))
      (node (ref "U$5") (pin "19") (pinfunction "DCPRG_19") (pintype "input"))
      (node (ref "U$6") (pin "19") (pinfunction "DCPRG_19") (pintype "input"))
      (node (ref "U$7") (pin "19") (pinfunction "DCPRG_19") (pintype "input"))
    )
    (net (code "99") (name "Net-(IC1-PD7(AIN1))") (class "Default")
      (node (ref "IC1") (pin "13") (pinfunction "PD7(AIN1)_13") (pintype "bidirectional"))
      (node (ref "U$1") (pin "27") (pinfunction "VPRG_27") (pintype "input"))
      (node (ref "U$5") (pin "27") (pinfunction "VPRG_27") (pintype "input"))
      (node (ref "U$6") (pin "27") (pinfunction "VPRG_27") (pintype "input"))
      (node (ref "U$7") (pin "27") (pinfunction "VPRG_27") (pintype "input"))
    )
    (net (code "100") (name "Net-(IC2A-0)") (class "Default")
      (node (ref "IC2") (pin "1") (pinfunction "0_1") (pintype "output"))
      (node (ref "Q2") (pin "4") (pinfunction "G2_4") (pintype "passive"))
      (node (ref "R18") (pin "1") (pinfunction "1_1") (pintype "passive"))
    )
    (net (code "101") (name "Net-(IC2A-1)") (class "Default")
      (node (ref "IC2") (pin "2") (pinfunction "1_2") (pintype "output"))
      (node (ref "Q2") (pin "2") (pinfunction "G1_2") (pintype "passive"))
      (node (ref "R17") (pin "1") (pinfunction "1_1") (pintype "passive"))
    )
    (net (code "102") (name "Net-(IC2A-2)") (class "Default")
      (node (ref "IC2") (pin "3") (pinfunction "2_3") (pintype "output"))
      (node (ref "Q3") (pin "4") (pinfunction "G2_4") (pintype "passive"))
      (node (ref "R8") (pin "1") (pinfunction "1_1") (pintype "passive"))
    )
    (net (code "103") (name "Net-(IC2A-3)") (class "Default")
      (node (ref "IC2") (pin "4") (pinfunction "3_4") (pintype "output"))
      (node (ref "Q3") (pin "2") (pinfunction "G1_2") (pintype "passive"))
      (node (ref "R7") (pin "1") (pinfunction "1_1") (pintype "passive"))
    )
    (net (code "104") (name "Net-(IC2A-4)") (class "Default")
      (node (ref "IC2") (pin "5") (pinfunction "4_5") (pintype "output"))
      (node (ref "Q4") (pin "4") (pinfunction "G2_4") (pintype "passive"))
      (node (ref "R12") (pin "1") (pinfunction "1_1") (pintype "passive"))
    )
    (net (code "105") (name "Net-(IC2A-5)") (class "Default")
      (node (ref "IC2") (pin "6") (pinfunction "5_6") (pintype "output"))
      (node (ref "Q4") (pin "2") (pinfunction "G1_2") (pintype "passive"))
      (node (ref "R11") (pin "1") (pinfunction "1_1") (pintype "passive"))
    )
    (net (code "106") (name "Net-(IC2A-6)") (class "Default")
      (node (ref "IC2") (pin "7") (pinfunction "6_7") (pintype "output"))
      (node (ref "Q5") (pin "4") (pinfunction "G2_4") (pintype "passive"))
      (node (ref "R21") (pin "1") (pinfunction "1_1") (pintype "passive"))
    )
    (net (code "107") (name "Net-(IC2A-7)") (class "Default")
      (node (ref "IC2") (pin "8") (pinfunction "7_8") (pintype "output"))
      (node (ref "Q5") (pin "2") (pinfunction "G1_2") (pintype "passive"))
      (node (ref "R15") (pin "1") (pinfunction "1_1") (pintype "passive"))
    )
    (net (code "108") (name "Net-(IC2A-8)") (class "Default")
      (node (ref "IC2") (pin "9") (pinfunction "8_9") (pintype "output"))
      (node (ref "Q6") (pin "4") (pinfunction "G2_4") (pintype "passive"))
      (node (ref "R25") (pin "1") (pinfunction "1_1") (pintype "passive"))
    )
    (net (code "109") (name "Net-(IC2A-9)") (class "Default")
      (node (ref "IC2") (pin "10") (pinfunction "9_10") (pintype "output"))
      (node (ref "Q6") (pin "2") (pinfunction "G1_2") (pintype "passive"))
      (node (ref "R24") (pin "1") (pinfunction "1_1") (pintype "passive"))
    )
    (net (code "110") (name "Net-(IC2A-10)") (class "Default")
      (node (ref "IC2") (pin "11") (pinfunction "10_11") (pintype "output"))
      (node (ref "Q7") (pin "4") (pinfunction "G2_4") (pintype "passive"))
      (node (ref "R29") (pin "1") (pinfunction "1_1") (pintype "passive"))
    )
    (net (code "111") (name "Net-(IC2A-11)") (class "Default")
      (node (ref "IC2") (pin "13") (pinfunction "11_13") (pintype "output"))
      (node (ref "Q7") (pin "2") (pinfunction "G1_2") (pintype "passive"))
      (node (ref "R28") (pin "1") (pinfunction "1_1") (pintype "passive"))
    )
    (net (code "112") (name "Net-(U$1-IREF)") (class "Default")
      (node (ref "R5") (pin "2") (pinfunction "2_2") (pintype "passive"))
      (node (ref "U$1") (pin "20") (pinfunction "IREF_20") (pintype "power_in"))
    )
    (net (code "113") (name "Net-(U$1-SIN)") (class "Default")
      (node (ref "U$1") (pin "26") (pinfunction "SIN_26") (pintype "input"))
      (node (ref "U$7") (pin "17") (pinfunction "SOUT_17") (pintype "output"))
    )
    (net (code "114") (name "Net-(U$5-IREF)") (class "Default")
      (node (ref "R2") (pin "2") (pinfunction "2_2") (pintype "passive"))
      (node (ref "U$5") (pin "20") (pinfunction "IREF_20") (pintype "power_in"))
    )
    (net (code "115") (name "Net-(U$5-SOUT)") (class "Default")
      (node (ref "U$5") (pin "17") (pinfunction "SOUT_17") (pintype "output"))
      (node (ref "U$6") (pin "26") (pinfunction "SIN_26") (pintype "input"))
    )
    (net (code "116") (name "Net-(U$6-IREF)") (class "Default")
      (node (ref "R3") (pin "2") (pinfunction "2_2") (pintype "passive"))
      (node (ref "U$6") (pin "20") (pinfunction "IREF_20") (pintype "power_in"))
    )
    (net (code "117") (name "Net-(U$6-SOUT)") (class "Default")
      (node (ref "U$6") (pin "17") (pinfunction "SOUT_17") (pintype "output"))
      (node (ref "U$7") (pin "26") (pinfunction "SIN_26") (pintype "input"))
    )
    (net (code "118") (name "Net-(U$7-IREF)") (class "Default")
      (node (ref "R4") (pin "2") (pinfunction "2_2") (pintype "passive"))
      (node (ref "U$7") (pin "20") (pinfunction "IREF_20") (pintype "power_in"))
    )
    (net (code "119") (name "unconnected-(IC1-PB4(MISO)-Pad18)") (class "Default")
      (node (ref "IC1") (pin "18") (pinfunction "PB4(MISO)_18") (pintype "bidirectional"))
    )
    (net (code "120") (name "unconnected-(IC1-PD2(INT0)-Pad4)") (class "Default")
      (node (ref "IC1") (pin "4") (pinfunction "PD2(INT0)_4") (pintype "bidirectional"))
    )
    (net (code "121") (name "unconnected-(IC1-PD3(INT1)-Pad5)") (class "Default")
      (node (ref "IC1") (pin "5") (pinfunction "PD3(INT1)_5") (pintype "bidirectional"))
    )
    (net (code "122") (name "unconnected-(IC1-PD5(T1)-Pad11)") (class "Default")
      (node (ref "IC1") (pin "11") (pinfunction "PD5(T1)_11") (pintype "bidirectional"))
    )
    (net (code "123") (name "unconnected-(IC1-PD6(AIN0)-Pad12)") (class "Default")
      (node (ref "IC1") (pin "12") (pinfunction "PD6(AIN0)_12") (pintype "bidirectional"))
    )
    (net (code "124") (name "unconnected-(IC2A-12-Pad14)") (class "Default")
      (node (ref "IC2") (pin "14") (pinfunction "12_14") (pintype "output"))
    )
    (net (code "125") (name "unconnected-(IC2A-13-Pad15)") (class "Default")
      (node (ref "IC2") (pin "15") (pinfunction "13_15") (pintype "output"))
    )
    (net (code "126") (name "unconnected-(IC2A-14-Pad16)") (class "Default")
      (node (ref "IC2") (pin "16") (pinfunction "14_16") (pintype "output"))
    )
    (net (code "127") (name "unconnected-(IC2A-15-Pad17)") (class "Default")
      (node (ref "IC2") (pin "17") (pinfunction "15_17") (pintype "output"))
    )
    (net (code "128") (name "unconnected-(U$1-SOUT-Pad17)") (class "Default")
      (node (ref "U$1") (pin "17") (pinfunction "SOUT_17") (pintype "output"))
    )
    (net (code "129") (name "unconnected-(U$1-XERR-Pad16)") (class "Default")
      (node (ref "U$1") (pin "16") (pinfunction "XERR_16") (pintype "output"))
    )
    (net (code "130") (name "unconnected-(U$5-XERR-Pad16)") (class "Default")
      (node (ref "U$5") (pin "16") (pinfunction "XERR_16") (pintype "output"))
    )
    (net (code "131") (name "unconnected-(U$6-XERR-Pad16)") (class "Default")
      (node (ref "U$6") (pin "16") (pinfunction "XERR_16") (pintype "output"))
    )
    (net (code "132") (name "unconnected-(U$7-XERR-Pad16)") (class "Default")
      (node (ref "U$7") (pin "16") (pinfunction "XERR_16") (pintype "output"))
    )
    (net (code "133") (name "unconnected-(X2A-S-Pad1)") (class "Default")
      (node (ref "X2") (pin "1") (pinfunction "S_1") (pintype "passive"))
    )
    (net (code "134") (name "unconnected-(X2C-S-Pad3)") (class "Default")
      (node (ref "X2") (pin "3") (pinfunction "S_3") (pintype "passive"))
    )
  )
)
